# SDvp.net
KiCad netlist of a schematic drawn in Altium Designer
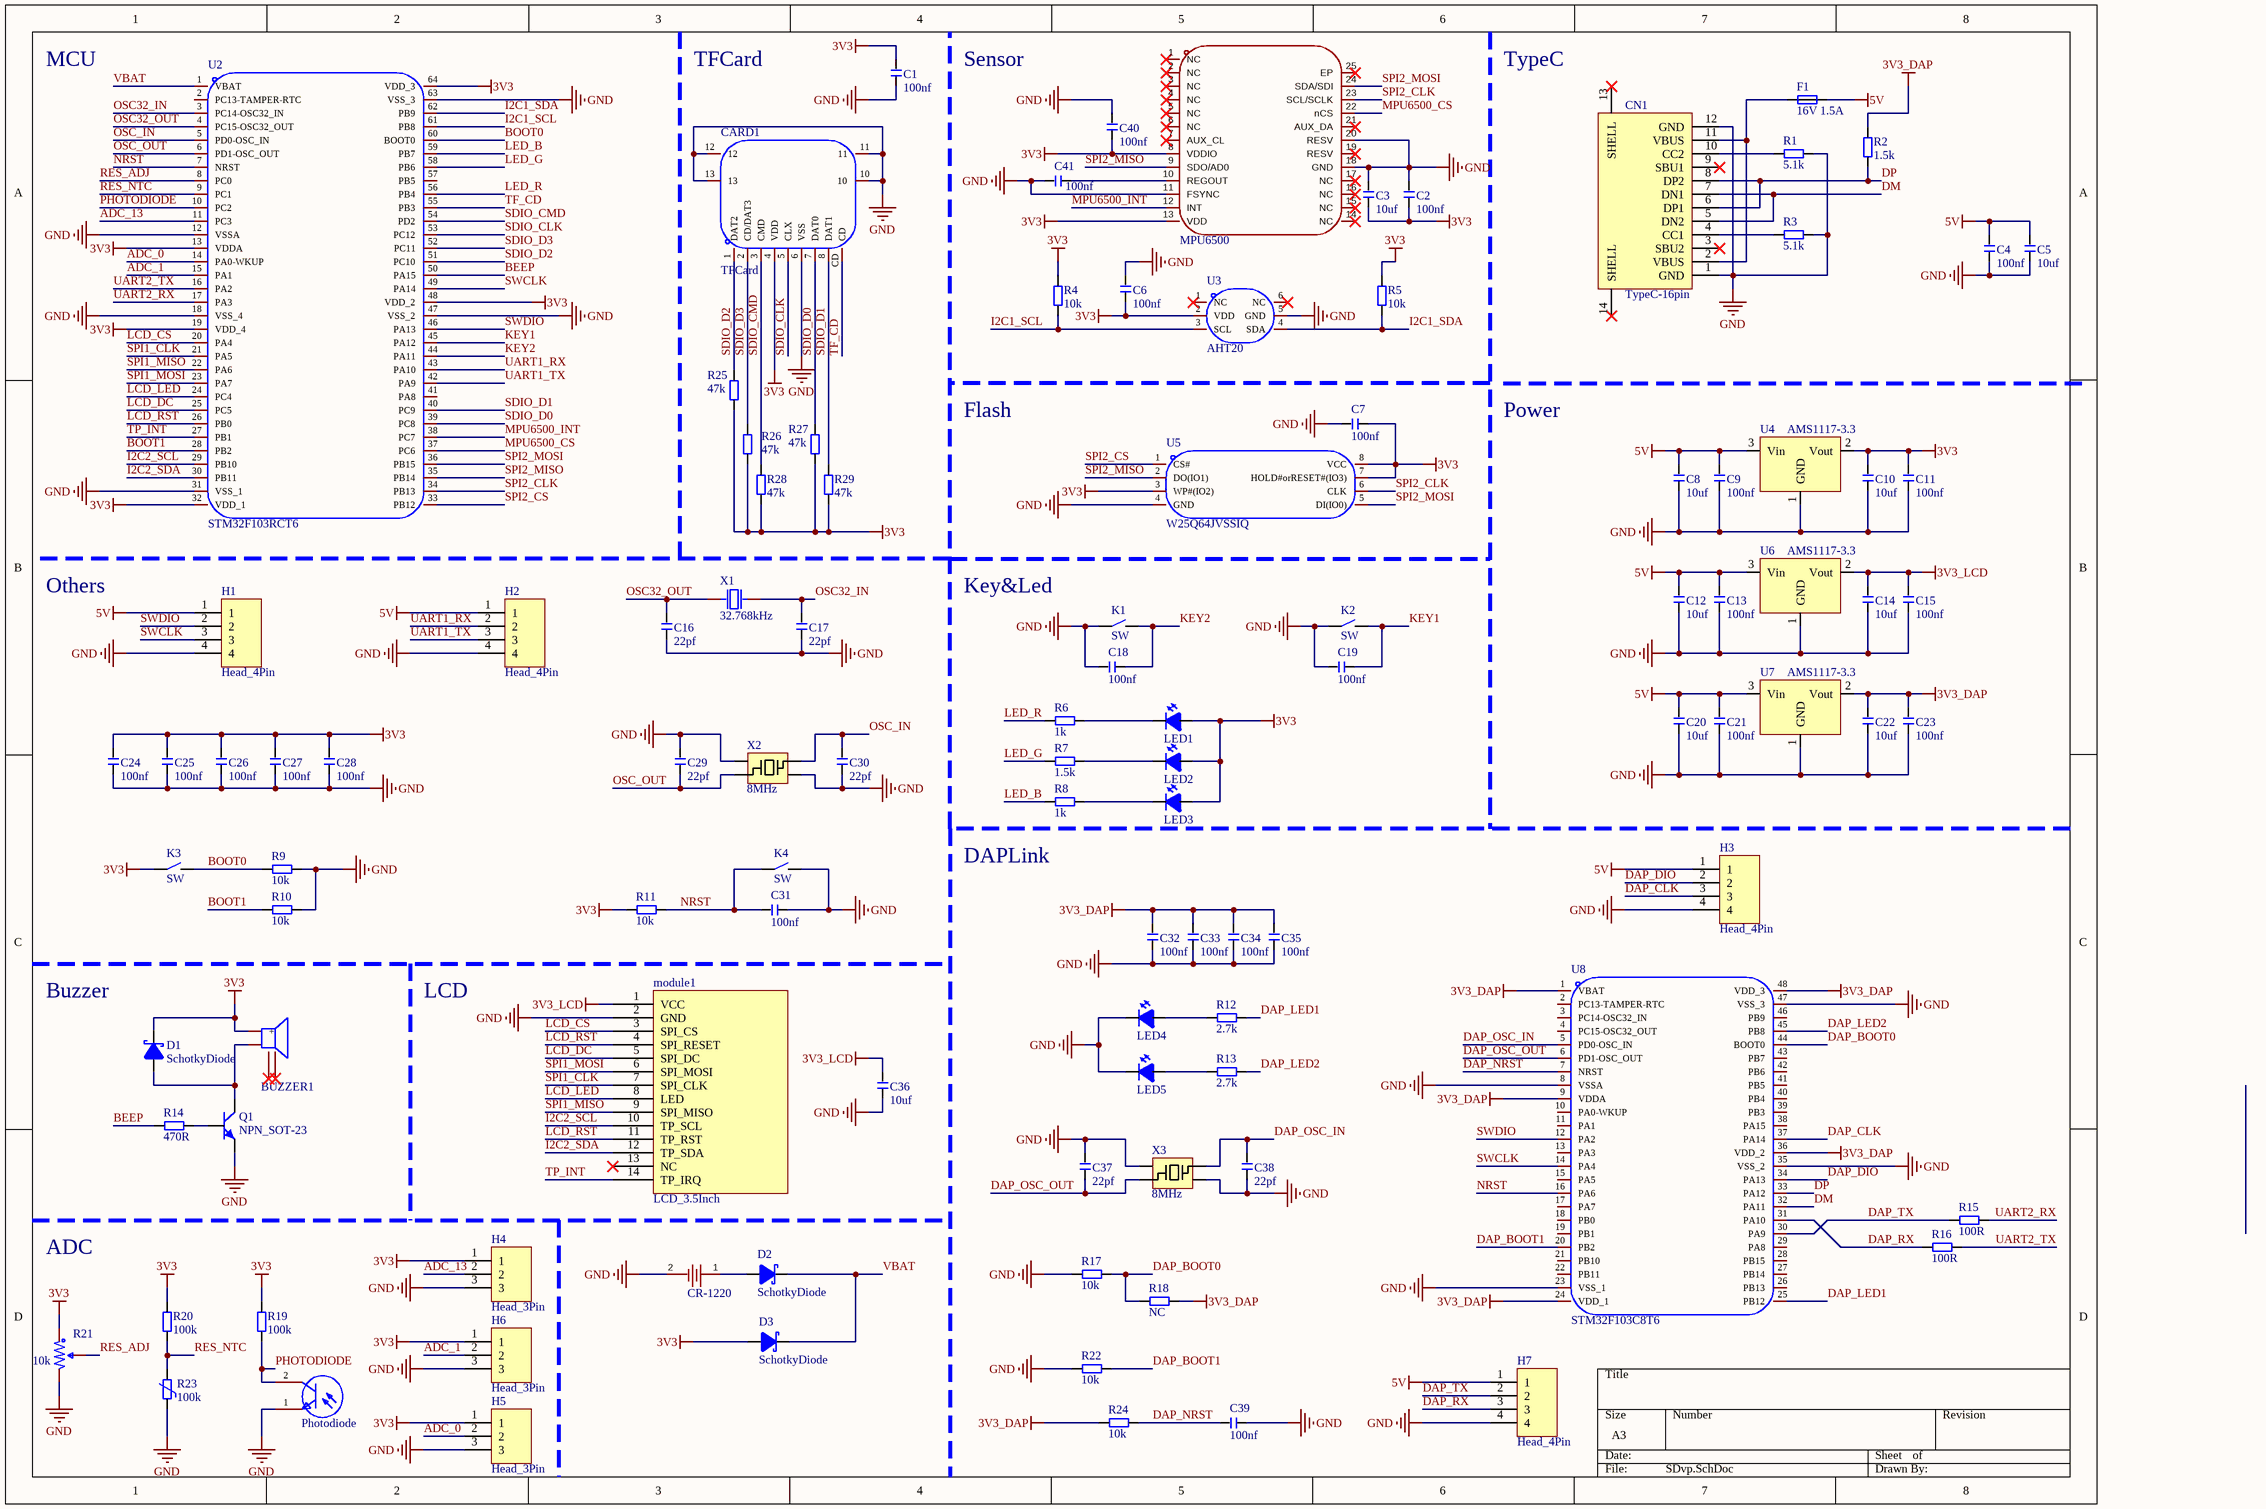
[diagram p0: SDvp.SchDoc]

(export (version "E")
  (design (tool "Eeschema 10.0.6"))
  (components
    (comp (ref "BUZZER1")
      (value "PassiveBuzzer")
      (footprint "BUZ-SMD_8530")
      (libsource (lib "IC") (part "PassiveBuzzer"))
    )
    (comp (ref "C1")
      (value "100nf")
      (footprint "CAP0603")
      (description "MLCC无极性电容")
      (libsource (lib "LCR") (part "Cap"))
    )
    (comp (ref "C2")
      (value "100nf")
      (footprint "CAP0603")
      (description "MLCC无极性电容")
      (libsource (lib "LCR") (part "Cap"))
    )
    (comp (ref "C3")
      (value "10uf")
      (footprint "CAP0603")
      (description "MLCC无极性电容")
      (libsource (lib "LCR") (part "Cap"))
    )
    (comp (ref "C4")
      (value "100nf")
      (footprint "CAP0603")
      (description "MLCC无极性电容")
      (libsource (lib "LCR") (part "Cap"))
    )
    (comp (ref "C5")
      (value "10uf")
      (footprint "CAP0603")
      (description "MLCC无极性电容")
      (libsource (lib "LCR") (part "Cap"))
    )
    (comp (ref "C6")
      (value "100nf")
      (footprint "CAP0603")
      (description "MLCC无极性电容")
      (libsource (lib "LCR") (part "Cap"))
    )
    (comp (ref "C7")
      (value "100nf")
      (footprint "CAP0603")
      (description "MLCC无极性电容")
      (libsource (lib "LCR") (part "Cap"))
    )
    (comp (ref "C8")
      (value "10uf")
      (footprint "CAP0603")
      (description "MLCC无极性电容")
      (libsource (lib "LCR") (part "Cap"))
    )
    (comp (ref "C9")
      (value "100nf")
      (footprint "CAP0603")
      (description "MLCC无极性电容")
      (libsource (lib "LCR") (part "Cap"))
    )
    (comp (ref "C10")
      (value "10uf")
      (footprint "CAP0603")
      (description "MLCC无极性电容")
      (libsource (lib "LCR") (part "Cap"))
    )
    (comp (ref "C11")
      (value "100nf")
      (footprint "CAP0603")
      (description "MLCC无极性电容")
      (libsource (lib "LCR") (part "Cap"))
    )
    (comp (ref "C12")
      (value "10uf")
      (footprint "CAP0603")
      (description "MLCC无极性电容")
      (libsource (lib "LCR") (part "Cap"))
    )
    (comp (ref "C13")
      (value "100nf")
      (footprint "CAP0603")
      (description "MLCC无极性电容")
      (libsource (lib "LCR") (part "Cap"))
    )
    (comp (ref "C14")
      (value "10uf")
      (footprint "CAP0603")
      (description "MLCC无极性电容")
      (libsource (lib "LCR") (part "Cap"))
    )
    (comp (ref "C15")
      (value "100nf")
      (footprint "CAP0603")
      (description "MLCC无极性电容")
      (libsource (lib "LCR") (part "Cap"))
    )
    (comp (ref "C16")
      (value "22pf")
      (footprint "CAP0603")
      (description "MLCC无极性电容")
      (libsource (lib "LCR") (part "Cap"))
    )
    (comp (ref "C17")
      (value "22pf")
      (footprint "CAP0603")
      (description "MLCC无极性电容")
      (libsource (lib "LCR") (part "Cap"))
    )
    (comp (ref "C18")
      (value "100nf")
      (footprint "CAP0603")
      (description "MLCC无极性电容")
      (libsource (lib "LCR") (part "Cap"))
    )
    (comp (ref "C19")
      (value "100nf")
      (footprint "CAP0603")
      (description "MLCC无极性电容")
      (libsource (lib "LCR") (part "Cap"))
    )
    (comp (ref "C20")
      (value "10uf")
      (footprint "CAP0603")
      (description "MLCC无极性电容")
      (libsource (lib "LCR") (part "Cap"))
    )
    (comp (ref "C21")
      (value "100nf")
      (footprint "CAP0603")
      (description "MLCC无极性电容")
      (libsource (lib "LCR") (part "Cap"))
    )
    (comp (ref "C22")
      (value "10uf")
      (footprint "CAP0603")
      (description "MLCC无极性电容")
      (libsource (lib "LCR") (part "Cap"))
    )
    (comp (ref "C23")
      (value "100nf")
      (footprint "CAP0603")
      (description "MLCC无极性电容")
      (libsource (lib "LCR") (part "Cap"))
    )
    (comp (ref "C24")
      (value "100nf")
      (footprint "CAP0603")
      (description "MLCC无极性电容")
      (libsource (lib "LCR") (part "Cap"))
    )
    (comp (ref "C25")
      (value "100nf")
      (footprint "CAP0603")
      (description "MLCC无极性电容")
      (libsource (lib "LCR") (part "Cap"))
    )
    (comp (ref "C26")
      (value "100nf")
      (footprint "CAP0603")
      (description "MLCC无极性电容")
      (libsource (lib "LCR") (part "Cap"))
    )
    (comp (ref "C27")
      (value "100nf")
      (footprint "CAP0603")
      (description "MLCC无极性电容")
      (libsource (lib "LCR") (part "Cap"))
    )
    (comp (ref "C28")
      (value "100nf")
      (footprint "CAP0603")
      (description "MLCC无极性电容")
      (libsource (lib "LCR") (part "Cap"))
    )
    (comp (ref "C29")
      (value "22pf")
      (footprint "CAP0603")
      (description "MLCC无极性电容")
      (libsource (lib "LCR") (part "Cap"))
    )
    (comp (ref "C30")
      (value "22pf")
      (footprint "CAP0603")
      (description "MLCC无极性电容")
      (libsource (lib "LCR") (part "Cap"))
    )
    (comp (ref "C31")
      (value "100nf")
      (footprint "CAP0603")
      (description "MLCC无极性电容")
      (libsource (lib "LCR") (part "Cap"))
    )
    (comp (ref "C32")
      (value "100nf")
      (footprint "CAP0603")
      (description "MLCC无极性电容")
      (libsource (lib "LCR") (part "Cap"))
    )
    (comp (ref "C33")
      (value "100nf")
      (footprint "CAP0603")
      (description "MLCC无极性电容")
      (libsource (lib "LCR") (part "Cap"))
    )
    (comp (ref "C34")
      (value "100nf")
      (footprint "CAP0603")
      (description "MLCC无极性电容")
      (libsource (lib "LCR") (part "Cap"))
    )
    (comp (ref "C35")
      (value "100nf")
      (footprint "CAP0603")
      (description "MLCC无极性电容")
      (libsource (lib "LCR") (part "Cap"))
    )
    (comp (ref "C36")
      (value "10uf")
      (footprint "CAP0603")
      (description "MLCC无极性电容")
      (libsource (lib "LCR") (part "Cap"))
    )
    (comp (ref "C37")
      (value "22pf")
      (footprint "CAP0603")
      (description "MLCC无极性电容")
      (libsource (lib "LCR") (part "Cap"))
    )
    (comp (ref "C38")
      (value "22pf")
      (footprint "CAP0603")
      (description "MLCC无极性电容")
      (libsource (lib "LCR") (part "Cap"))
    )
    (comp (ref "C39")
      (value "100nf")
      (footprint "CAP0603")
      (description "MLCC无极性电容")
      (libsource (lib "LCR") (part "Cap"))
    )
    (comp (ref "C40")
      (value "100nf")
      (footprint "CAP0603")
      (description "MLCC无极性电容")
      (libsource (lib "LCR") (part "Cap"))
    )
    (comp (ref "C41")
      (value "100nf")
      (footprint "CAP0603")
      (description "MLCC无极性电容")
      (libsource (lib "LCR") (part "Cap"))
    )
    (comp (ref "CARD1")
      (value "TFCard")
      (footprint "TF-SMD")
      (libsource (lib "Connector&Key") (part "TFCard"))
    )
    (comp (ref "CN1")
      (value "TypeC-16pin")
      (footprint "USB-C-SMD_16Pin")
      (libsource (lib "Connector&Key") (part "TypeC-16pin"))
    )
    (comp (ref "D1")
      (value "SchotkyDiode")
      (footprint "SOD-323")
      (description "肖特基二极管")
      (libsource (lib "Transistor") (part "SchotkyDiode"))
    )
    (comp (ref "D2")
      (value "SchotkyDiode")
      (footprint "SOD-323")
      (description "肖特基二极管")
      (libsource (lib "Transistor") (part "SchotkyDiode"))
    )
    (comp (ref "D3")
      (value "SchotkyDiode")
      (footprint "SOD-323")
      (description "肖特基二极管")
      (libsource (lib "Transistor") (part "SchotkyDiode"))
    )
    (comp (ref "F1")
      (value "16V 1.5A")
      (footprint "FUSE1206")
      (description "保险丝")
      (libsource (lib "LCR") (part "Fuse"))
    )
    (comp (ref "H1")
      (value "Head_4Pin")
      (footprint "2.54排针_4PIN")
      (libsource (lib "Connector&Key") (part "Head_4Pin"))
    )
    (comp (ref "H2")
      (value "Head_4Pin")
      (footprint "XH2.54_4Pin")
      (libsource (lib "Connector&Key") (part "Head_4Pin"))
    )
    (comp (ref "H3")
      (value "Head_4Pin")
      (footprint "2.54排针_4PIN")
      (libsource (lib "Connector&Key") (part "Head_4Pin"))
    )
    (comp (ref "H4")
      (value "Head_3Pin")
      (footprint "XH2.54_3Pin")
      (libsource (lib "Connector&Key") (part "Head_3Pin"))
    )
    (comp (ref "H5")
      (value "Head_3Pin")
      (footprint "XH2.54_3Pin")
      (libsource (lib "Connector&Key") (part "Head_3Pin"))
    )
    (comp (ref "H6")
      (value "Head_3Pin")
      (footprint "XH2.54_3Pin")
      (libsource (lib "Connector&Key") (part "Head_3Pin"))
    )
    (comp (ref "H7")
      (value "Head_4Pin")
      (footprint "2.54排针_4PIN")
      (libsource (lib "Connector&Key") (part "Head_4Pin"))
    )
    (comp (ref "K1")
      (value "SW")
      (footprint "SW-SMD_3425")
      (description "轻触开关")
      (libsource (lib "Connector&Key") (part "SW"))
    )
    (comp (ref "K2")
      (value "SW")
      (footprint "SW-SMD_3425")
      (description "轻触开关")
      (libsource (lib "Connector&Key") (part "SW"))
    )
    (comp (ref "K3")
      (value "SW")
      (footprint "SW-SMD_3425")
      (description "轻触开关")
      (libsource (lib "Connector&Key") (part "SW"))
    )
    (comp (ref "K4")
      (value "SW")
      (footprint "SW-SMD_3425")
      (description "轻触开关")
      (libsource (lib "Connector&Key") (part "SW"))
    )
    (comp (ref "LED1")
      (value "LED_R")
      (footprint "LED0603")
      (description "发光二极管")
      (libsource (lib "Transistor") (part "LED"))
    )
    (comp (ref "LED2")
      (value "LED_G")
      (footprint "LED0603")
      (description "发光二极管")
      (libsource (lib "Transistor") (part "LED"))
    )
    (comp (ref "LED3")
      (value "LED_B")
      (footprint "LED0603")
      (description "发光二极管")
      (libsource (lib "Transistor") (part "LED"))
    )
    (comp (ref "LED4")
      (value "LED")
      (footprint "LED0603")
      (description "发光二极管")
      (libsource (lib "Transistor") (part "LED"))
    )
    (comp (ref "LED5")
      (value "LED")
      (footprint "LED0603")
      (description "发光二极管")
      (libsource (lib "Transistor") (part "LED"))
    )
    (comp (ref "module1")
      (value "LCD_3.5Inch")
      (footprint "LCD_3.5Inch")
      (libsource (lib "module") (part "LCD_3.5Inch"))
    )
    (comp (ref "Q1")
      (value "NPN_SOT-23")
      (footprint "SOT-23-3")
      (description "三极管")
      (libsource (lib "Transistor") (part "NPN_SOT-23"))
    )
    (comp (ref "R1")
      (value "5.1k")
      (footprint "RES0603")
      (description "电阻")
      (libsource (lib "LCR") (part "Res"))
    )
    (comp (ref "R2")
      (value "1.5k")
      (footprint "RES0603")
      (description "电阻")
      (libsource (lib "LCR") (part "Res"))
    )
    (comp (ref "R3")
      (value "5.1k")
      (footprint "RES0603")
      (description "电阻")
      (libsource (lib "LCR") (part "Res"))
    )
    (comp (ref "R4")
      (value "10k")
      (footprint "RES0603")
      (description "电阻")
      (libsource (lib "LCR") (part "Res"))
    )
    (comp (ref "R5")
      (value "10k")
      (footprint "RES0603")
      (description "电阻")
      (libsource (lib "LCR") (part "Res"))
    )
    (comp (ref "R6")
      (value "1k")
      (footprint "RES0603")
      (description "电阻")
      (libsource (lib "LCR") (part "Res"))
    )
    (comp (ref "R7")
      (value "1.5k")
      (footprint "RES0603")
      (description "电阻")
      (libsource (lib "LCR") (part "Res"))
    )
    (comp (ref "R8")
      (value "1k")
      (footprint "RES0603")
      (description "电阻")
      (libsource (lib "LCR") (part "Res"))
    )
    (comp (ref "R9")
      (value "10k")
      (footprint "RES0603")
      (description "电阻")
      (libsource (lib "LCR") (part "Res"))
    )
    (comp (ref "R10")
      (value "10k")
      (footprint "RES0603")
      (description "电阻")
      (libsource (lib "LCR") (part "Res"))
    )
    (comp (ref "R11")
      (value "10k")
      (footprint "RES0603")
      (description "电阻")
      (libsource (lib "LCR") (part "Res"))
    )
    (comp (ref "R12")
      (value "2.7k")
      (footprint "RES0603")
      (description "电阻")
      (libsource (lib "LCR") (part "Res"))
    )
    (comp (ref "R13")
      (value "2.7k")
      (footprint "RES0603")
      (description "电阻")
      (libsource (lib "LCR") (part "Res"))
    )
    (comp (ref "R14")
      (value "470R")
      (footprint "RES0603")
      (description "电阻")
      (libsource (lib "LCR") (part "Res"))
    )
    (comp (ref "R15")
      (value "100R")
      (footprint "RES0603")
      (description "电阻")
      (libsource (lib "LCR") (part "Res"))
    )
    (comp (ref "R16")
      (value "100R")
      (footprint "RES0603")
      (description "电阻")
      (libsource (lib "LCR") (part "Res"))
    )
    (comp (ref "R17")
      (value "10k")
      (footprint "RES0603")
      (description "电阻")
      (libsource (lib "LCR") (part "Res"))
    )
    (comp (ref "R18")
      (value "NC")
      (footprint "RES0603")
      (description "电阻")
      (libsource (lib "LCR") (part "Res"))
    )
    (comp (ref "R19")
      (value "100k")
      (footprint "RES0603")
      (description "电阻")
      (libsource (lib "LCR") (part "Res"))
    )
    (comp (ref "R20")
      (value "100k")
      (footprint "RES0603")
      (description "电阻")
      (libsource (lib "LCR") (part "Res"))
    )
    (comp (ref "R21")
      (value "10k")
      (footprint "RES-ADJ-BuleWhite")
      (description "可调电位器")
      (libsource (lib "LCR") (part "RES_ADJ"))
    )
    (comp (ref "R22")
      (value "10k")
      (footprint "RES0603")
      (description "电阻")
      (libsource (lib "LCR") (part "Res"))
    )
    (comp (ref "R23")
      (value "100k")
      (footprint "RES0603")
      (description "热敏电阻")
      (libsource (lib "LCR") (part "RES_NTC"))
    )
    (comp (ref "R24")
      (value "10k")
      (footprint "RES0603")
      (description "电阻")
      (libsource (lib "LCR") (part "Res"))
    )
    (comp (ref "R25")
      (value "47k")
      (footprint "RES0603")
      (description "电阻")
      (libsource (lib "LCR") (part "Res"))
    )
    (comp (ref "R26")
      (value "47k")
      (footprint "RES0603")
      (description "电阻")
      (libsource (lib "LCR") (part "Res"))
    )
    (comp (ref "R27")
      (value "47k")
      (footprint "RES0603")
      (description "电阻")
      (libsource (lib "LCR") (part "Res"))
    )
    (comp (ref "R28")
      (value "47k")
      (footprint "RES0603")
      (description "电阻")
      (libsource (lib "LCR") (part "Res"))
    )
    (comp (ref "R29")
      (value "47k")
      (footprint "RES0603")
      (description "电阻")
      (libsource (lib "LCR") (part "Res"))
    )
    (comp (ref "U1")
      (value "MPU6500")
      (footprint "QFN-24")
      (description "陀螺仪芯片")
      (libsource (lib "IC") (part "MPU6500"))
    )
    (comp (ref "U2")
      (value "STM32F103RCT6")
      (footprint "LQFP-64")
      (description "STM32F103")
      (libsource (lib "IC") (part "STM32F103RCT6"))
    )
    (comp (ref "U3")
      (value "AHT20")
      (footprint "AHT20")
      (description "温湿度芯片")
      (libsource (lib "IC") (part "AHT20"))
    )
    (comp (ref "U4")
      (value "AMS1117-3.3")
      (footprint "SOT223")
      (description "降压芯片")
      (libsource (lib "IC") (part "AMS1117-3.3"))
    )
    (comp (ref "U5")
      (value "W25Q64JVSSIQ")
      (footprint "SOIC-8")
      (description "FLASH芯片")
      (libsource (lib "IC") (part "W25Q64JVSSIQ"))
    )
    (comp (ref "U6")
      (value "AMS1117-3.3")
      (footprint "SOT223")
      (description "降压芯片")
      (libsource (lib "IC") (part "AMS1117-3.3"))
    )
    (comp (ref "U7")
      (value "AMS1117-3.3")
      (footprint "SOT223")
      (description "降压芯片")
      (libsource (lib "IC") (part "AMS1117-3.3"))
    )
    (comp (ref "U8")
      (value "STM32F103C8T6")
      (footprint "LQFP-48")
      (description "STM32F103")
      (libsource (lib "IC") (part "STM32F103C8T6"))
    )
    (comp (ref "U9")
      (value "Photodiode")
      (footprint "Photodiode0603")
      (description "光敏二极管")
      (libsource (lib "Transistor") (part "Photodiode"))
    )
    (comp (ref "U10")
      (value "CR-1220")
      (footprint "BAT-SMD_CR1220")
      (description "CR-1220电池座")
      (libsource (lib "Connector&Key") (part "CR-1220"))
    )
    (comp (ref "X1")
      (value "32.768kHz")
      (footprint "XTAL_3215")
      (description "无源晶振3215")
      (libsource (lib "IC") (part "XTAL_3215"))
    )
    (comp (ref "X2") (value "8MHz") (footprint "XTAL_3225") (libsource (lib "IC") (part "XTAL_无源4脚")))
    (comp (ref "X3") (value "8MHz") (footprint "XTAL_3225") (libsource (lib "IC") (part "XTAL_无源4脚")))
  )
  (nets
    (net (code "1") (name "/ADC_0") (class "Default")
      (node (ref "H5") (pin "2") (pinfunction "2_2") (pintype "passive"))
      (node (ref "U2") (pin "14") (pinfunction "PA0-WKUP_14") (pintype "passive"))
    )
    (net (code "2") (name "/ADC_1") (class "Default")
      (node (ref "H6") (pin "2") (pinfunction "2_2") (pintype "passive"))
      (node (ref "U2") (pin "15") (pinfunction "PA1_15") (pintype "passive"))
    )
    (net (code "3") (name "/ADC_13") (class "Default")
      (node (ref "H4") (pin "2") (pinfunction "2_2") (pintype "passive"))
      (node (ref "U2") (pin "11") (pinfunction "PC3_11") (pintype "passive"))
    )
    (net (code "4") (name "/BEEP") (class "Default")
      (node (ref "R14") (pin "1") (pinfunction "1_1") (pintype "passive"))
      (node (ref "U2") (pin "50") (pinfunction "PA15_50") (pintype "passive"))
    )
    (net (code "5") (name "/BOOT0") (class "Default")
      (node (ref "K3") (pin "2") (pinfunction "2_2") (pintype "passive"))
      (node (ref "R9") (pin "1") (pinfunction "1_1") (pintype "passive"))
      (node (ref "U2") (pin "60") (pinfunction "BOOT0_60") (pintype "passive"))
    )
    (net (code "6") (name "/BOOT1") (class "Default")
      (node (ref "R10") (pin "1") (pinfunction "1_1") (pintype "passive"))
      (node (ref "U2") (pin "28") (pinfunction "PB2_28") (pintype "passive"))
    )
    (net (code "7") (name "/DAP_BOOT0") (class "Default")
      (node (ref "R17") (pin "2") (pinfunction "2_2") (pintype "passive"))
      (node (ref "R18") (pin "1") (pinfunction "1_1") (pintype "passive"))
      (node (ref "U8") (pin "44") (pinfunction "BOOT0_44") (pintype "passive"))
    )
    (net (code "8") (name "/DAP_BOOT1") (class "Default")
      (node (ref "R22") (pin "2") (pinfunction "2_2") (pintype "passive"))
      (node (ref "U8") (pin "20") (pinfunction "PB2_20") (pintype "passive"))
    )
    (net (code "9") (name "/DAP_CLK") (class "Default")
      (node (ref "H3") (pin "3") (pinfunction "3_3") (pintype "passive"))
      (node (ref "U8") (pin "37") (pinfunction "PA14_37") (pintype "passive"))
    )
    (net (code "10") (name "/DAP_DIO") (class "Default")
      (node (ref "H3") (pin "2") (pinfunction "2_2") (pintype "passive"))
      (node (ref "U8") (pin "34") (pinfunction "PA13_34") (pintype "passive"))
    )
    (net (code "11") (name "/DAP_LED1") (class "Default")
      (node (ref "R12") (pin "2") (pinfunction "2_2") (pintype "passive"))
      (node (ref "U8") (pin "25") (pinfunction "PB12_25") (pintype "passive"))
    )
    (net (code "12") (name "/DAP_LED2") (class "Default")
      (node (ref "R13") (pin "2") (pinfunction "2_2") (pintype "passive"))
      (node (ref "U8") (pin "45") (pinfunction "PB8_45") (pintype "passive"))
    )
    (net (code "13") (name "/DAP_NRST") (class "Default")
      (node (ref "C39") (pin "1") (pinfunction "1_1") (pintype "passive"))
      (node (ref "R24") (pin "2") (pinfunction "2_2") (pintype "passive"))
      (node (ref "U8") (pin "7") (pinfunction "NRST_7") (pintype "passive"))
    )
    (net (code "14") (name "/DAP_OSC_IN") (class "Default")
      (node (ref "C38") (pin "2") (pinfunction "2_2") (pintype "passive"))
      (node (ref "U8") (pin "5") (pinfunction "PD0-OSC_IN_5") (pintype "passive"))
      (node (ref "X3") (pin "3") (pinfunction "3_3") (pintype "passive"))
    )
    (net (code "15") (name "/DAP_OSC_OUT") (class "Default")
      (node (ref "C37") (pin "1") (pinfunction "1_1") (pintype "passive"))
      (node (ref "U8") (pin "6") (pinfunction "PD1-OSC_OUT_6") (pintype "passive"))
      (node (ref "X3") (pin "1") (pinfunction "1_1") (pintype "passive"))
    )
    (net (code "16") (name "/DAP_RX") (class "Default")
      (node (ref "H7") (pin "3") (pinfunction "3_3") (pintype "passive"))
      (node (ref "R16") (pin "1") (pinfunction "1_1") (pintype "passive"))
      (node (ref "U8") (pin "31") (pinfunction "PA10_31") (pintype "passive"))
    )
    (net (code "17") (name "/DAP_TX") (class "Default")
      (node (ref "H7") (pin "2") (pinfunction "2_2") (pintype "passive"))
      (node (ref "R15") (pin "1") (pinfunction "1_1") (pintype "passive"))
      (node (ref "U8") (pin "30") (pinfunction "PA9_30") (pintype "passive"))
    )
    (net (code "18") (name "/DM") (class "Default")
      (node (ref "CN1") (pin "5") (pinfunction "DN2_5") (pintype "passive"))
      (node (ref "CN1") (pin "7") (pinfunction "DN1_7") (pintype "passive"))
      (node (ref "U8") (pin "32") (pinfunction "PA11_32") (pintype "passive"))
    )
    (net (code "19") (name "/DP") (class "Default")
      (node (ref "CN1") (pin "6") (pinfunction "DP1_6") (pintype "passive"))
      (node (ref "CN1") (pin "8") (pinfunction "DP2_8") (pintype "passive"))
      (node (ref "R2") (pin "2") (pinfunction "2_2") (pintype "passive"))
      (node (ref "U8") (pin "33") (pinfunction "PA12_33") (pintype "passive"))
    )
    (net (code "20") (name "/I2C1_SCL") (class "Default")
      (node (ref "R4") (pin "1") (pinfunction "1_1") (pintype "passive"))
      (node (ref "U2") (pin "61") (pinfunction "PB8_61") (pintype "passive"))
      (node (ref "U3") (pin "3") (pinfunction "SCL_3") (pintype "passive"))
    )
    (net (code "21") (name "/I2C1_SDA") (class "Default")
      (node (ref "R5") (pin "1") (pinfunction "1_1") (pintype "passive"))
      (node (ref "U2") (pin "62") (pinfunction "PB9_62") (pintype "passive"))
      (node (ref "U3") (pin "4") (pinfunction "SDA_4") (pintype "passive"))
    )
    (net (code "22") (name "/I2C2_SCL") (class "Default")
      (node (ref "U2") (pin "29") (pinfunction "PB10_29") (pintype "passive"))
      (node (ref "module1") (pin "10") (pinfunction "TP_SCL_10") (pintype "passive"))
    )
    (net (code "23") (name "/I2C2_SDA") (class "Default")
      (node (ref "U2") (pin "30") (pinfunction "PB11_30") (pintype "passive"))
      (node (ref "module1") (pin "12") (pinfunction "TP_SDA_12") (pintype "passive"))
    )
    (net (code "24") (name "/KEY1") (class "Default")
      (node (ref "C19") (pin "1") (pinfunction "1_1") (pintype "passive"))
      (node (ref "K2") (pin "2") (pinfunction "2_2") (pintype "passive"))
      (node (ref "U2") (pin "45") (pinfunction "PA12_45") (pintype "passive"))
    )
    (net (code "25") (name "/KEY2") (class "Default")
      (node (ref "C18") (pin "1") (pinfunction "1_1") (pintype "passive"))
      (node (ref "K1") (pin "2") (pinfunction "2_2") (pintype "passive"))
      (node (ref "U2") (pin "44") (pinfunction "PA11_44") (pintype "passive"))
    )
    (net (code "26") (name "/LCD_CS") (class "Default")
      (node (ref "U2") (pin "20") (pinfunction "PA4_20") (pintype "passive"))
      (node (ref "module1") (pin "3") (pinfunction "SPI_CS_3") (pintype "passive"))
    )
    (net (code "27") (name "/LCD_DC") (class "Default")
      (node (ref "U2") (pin "25") (pinfunction "PC5_25") (pintype "passive"))
      (node (ref "module1") (pin "5") (pinfunction "SPI_DC_5") (pintype "passive"))
    )
    (net (code "28") (name "/LCD_LED") (class "Default")
      (node (ref "U2") (pin "24") (pinfunction "PC4_24") (pintype "passive"))
      (node (ref "module1") (pin "8") (pinfunction "LED_8") (pintype "passive"))
    )
    (net (code "29") (name "/LCD_RST") (class "Default")
      (node (ref "U2") (pin "26") (pinfunction "PB0_26") (pintype "passive"))
      (node (ref "module1") (pin "11") (pinfunction "TP_RST_11") (pintype "passive"))
      (node (ref "module1") (pin "4") (pinfunction "SPI_RESET_4") (pintype "passive"))
    )
    (net (code "30") (name "/LED_B") (class "Default")
      (node (ref "R8") (pin "2") (pinfunction "2_2") (pintype "passive"))
      (node (ref "U2") (pin "59") (pinfunction "PB7_59") (pintype "passive"))
    )
    (net (code "31") (name "/LED_G") (class "Default")
      (node (ref "R7") (pin "2") (pinfunction "2_2") (pintype "passive"))
      (node (ref "U2") (pin "58") (pinfunction "PB6_58") (pintype "passive"))
    )
    (net (code "32") (name "/LED_R") (class "Default")
      (node (ref "R6") (pin "1") (pinfunction "1_1") (pintype "passive"))
      (node (ref "U2") (pin "56") (pinfunction "PB4_56") (pintype "passive"))
    )
    (net (code "33") (name "/MPU6500_CS") (class "Default")
      (node (ref "U1") (pin "22") (pinfunction "nCS_22") (pintype "passive"))
      (node (ref "U2") (pin "37") (pinfunction "PC6_37") (pintype "passive"))
    )
    (net (code "34") (name "/MPU6500_INT") (class "Default")
      (node (ref "U1") (pin "12") (pinfunction "INT_12") (pintype "passive"))
      (node (ref "U2") (pin "38") (pinfunction "PC7_38") (pintype "passive"))
    )
    (net (code "35") (name "/NRST") (class "Default")
      (node (ref "C31") (pin "1") (pinfunction "1_1") (pintype "passive"))
      (node (ref "K4") (pin "1") (pinfunction "1_1") (pintype "passive"))
      (node (ref "R11") (pin "2") (pinfunction "2_2") (pintype "passive"))
      (node (ref "U2") (pin "7") (pinfunction "NRST_7") (pintype "passive"))
      (node (ref "U8") (pin "16") (pinfunction "PA6_16") (pintype "passive"))
    )
    (net (code "36") (name "/OSC32_IN") (class "Default")
      (node (ref "C17") (pin "2") (pinfunction "2_2") (pintype "passive"))
      (node (ref "U2") (pin "3") (pinfunction "PC14-OSC32_IN_3") (pintype "passive"))
      (node (ref "X1") (pin "2") (pinfunction "OSC2_2") (pintype "passive"))
    )
    (net (code "37") (name "/OSC32_OUT") (class "Default")
      (node (ref "C16") (pin "2") (pinfunction "2_2") (pintype "passive"))
      (node (ref "U2") (pin "4") (pinfunction "PC15-OSC32_OUT_4") (pintype "passive"))
      (node (ref "X1") (pin "1") (pinfunction "OSC1_1") (pintype "passive"))
    )
    (net (code "38") (name "/OSC_IN") (class "Default")
      (node (ref "C30") (pin "2") (pinfunction "2_2") (pintype "passive"))
      (node (ref "U2") (pin "5") (pinfunction "PD0-OSC_IN_5") (pintype "passive"))
      (node (ref "X2") (pin "3") (pinfunction "3_3") (pintype "passive"))
    )
    (net (code "39") (name "/OSC_OUT") (class "Default")
      (node (ref "C29") (pin "1") (pinfunction "1_1") (pintype "passive"))
      (node (ref "U2") (pin "6") (pinfunction "PD1-OSC_OUT_6") (pintype "passive"))
      (node (ref "X2") (pin "1") (pinfunction "1_1") (pintype "passive"))
    )
    (net (code "40") (name "/PHOTODIODE") (class "Default")
      (node (ref "R19") (pin "1") (pinfunction "1_1") (pintype "passive"))
      (node (ref "U2") (pin "10") (pinfunction "PC2_10") (pintype "passive"))
      (node (ref "U9") (pin "2") (pinfunction "C_2") (pintype "passive"))
    )
    (net (code "41") (name "/RES_ADJ") (class "Default")
      (node (ref "R21") (pin "2") (pinfunction "2_2") (pintype "passive"))
      (node (ref "U2") (pin "8") (pinfunction "PC0_8") (pintype "passive"))
    )
    (net (code "42") (name "/RES_NTC") (class "Default")
      (node (ref "R20") (pin "1") (pinfunction "1_1") (pintype "passive"))
      (node (ref "R23") (pin "2") (pinfunction "2_2") (pintype "passive"))
      (node (ref "U2") (pin "9") (pinfunction "PC1_9") (pintype "passive"))
    )
    (net (code "43") (name "/SDIO_CLK") (class "Default")
      (node (ref "CARD1") (pin "5") (pinfunction "CLX_5") (pintype "passive"))
      (node (ref "U2") (pin "53") (pinfunction "PC12_53") (pintype "passive"))
    )
    (net (code "44") (name "/SDIO_CMD") (class "Default")
      (node (ref "CARD1") (pin "3") (pinfunction "CMD_3") (pintype "passive"))
      (node (ref "R28") (pin "2") (pinfunction "2_2") (pintype "passive"))
      (node (ref "U2") (pin "54") (pinfunction "PD2_54") (pintype "passive"))
    )
    (net (code "45") (name "/SDIO_D0") (class "Default")
      (node (ref "CARD1") (pin "7") (pinfunction "DAT0_7") (pintype "passive"))
      (node (ref "R27") (pin "2") (pinfunction "2_2") (pintype "passive"))
      (node (ref "U2") (pin "39") (pinfunction "PC8_39") (pintype "passive"))
    )
    (net (code "46") (name "/SDIO_D1") (class "Default")
      (node (ref "CARD1") (pin "8") (pinfunction "DAT1_8") (pintype "passive"))
      (node (ref "R29") (pin "2") (pinfunction "2_2") (pintype "passive"))
      (node (ref "U2") (pin "40") (pinfunction "PC9_40") (pintype "passive"))
    )
    (net (code "47") (name "/SDIO_D2") (class "Default")
      (node (ref "CARD1") (pin "1") (pinfunction "DAT2_1") (pintype "passive"))
      (node (ref "R25") (pin "2") (pinfunction "2_2") (pintype "passive"))
      (node (ref "U2") (pin "51") (pinfunction "PC10_51") (pintype "passive"))
    )
    (net (code "48") (name "/SDIO_D3") (class "Default")
      (node (ref "CARD1") (pin "2") (pinfunction "CD/DAT3_2") (pintype "passive"))
      (node (ref "R26") (pin "2") (pinfunction "2_2") (pintype "passive"))
      (node (ref "U2") (pin "52") (pinfunction "PC11_52") (pintype "passive"))
    )
    (net (code "49") (name "/SPI1_CLK") (class "Default")
      (node (ref "U2") (pin "21") (pinfunction "PA5_21") (pintype "passive"))
      (node (ref "module1") (pin "7") (pinfunction "SPI_CLK_7") (pintype "passive"))
    )
    (net (code "50") (name "/SPI1_MISO") (class "Default")
      (node (ref "U2") (pin "22") (pinfunction "PA6_22") (pintype "passive"))
      (node (ref "module1") (pin "9") (pinfunction "SPI_MISO_9") (pintype "passive"))
    )
    (net (code "51") (name "/SPI1_MOSI") (class "Default")
      (node (ref "U2") (pin "23") (pinfunction "PA7_23") (pintype "passive"))
      (node (ref "module1") (pin "6") (pinfunction "SPI_MOSI_6") (pintype "passive"))
    )
    (net (code "52") (name "/SPI2_CLK") (class "Default")
      (node (ref "U1") (pin "23") (pinfunction "SCL/SCLK_23") (pintype "passive"))
      (node (ref "U2") (pin "34") (pinfunction "PB13_34") (pintype "passive"))
      (node (ref "U5") (pin "6") (pinfunction "CLK_6") (pintype "passive"))
    )
    (net (code "53") (name "/SPI2_CS") (class "Default")
      (node (ref "U2") (pin "33") (pinfunction "PB12_33") (pintype "passive"))
      (node (ref "U5") (pin "1") (pinfunction "CS#_1") (pintype "passive"))
    )
    (net (code "54") (name "/SPI2_MISO") (class "Default")
      (node (ref "U1") (pin "9") (pinfunction "SDO/AD0_9") (pintype "passive"))
      (node (ref "U2") (pin "35") (pinfunction "PB14_35") (pintype "passive"))
      (node (ref "U5") (pin "2") (pinfunction "DO(IO1)_2") (pintype "passive"))
    )
    (net (code "55") (name "/SPI2_MOSI") (class "Default")
      (node (ref "U1") (pin "24") (pinfunction "SDA/SDI_24") (pintype "passive"))
      (node (ref "U2") (pin "36") (pinfunction "PB15_36") (pintype "passive"))
      (node (ref "U5") (pin "5") (pinfunction "DI(IO0)_5") (pintype "passive"))
    )
    (net (code "56") (name "/SWCLK") (class "Default")
      (node (ref "H1") (pin "3") (pinfunction "3_3") (pintype "passive"))
      (node (ref "U2") (pin "49") (pinfunction "PA14_49") (pintype "passive"))
      (node (ref "U8") (pin "14") (pinfunction "PA4_14") (pintype "passive"))
    )
    (net (code "57") (name "/SWDIO") (class "Default")
      (node (ref "H1") (pin "2") (pinfunction "2_2") (pintype "passive"))
      (node (ref "U2") (pin "46") (pinfunction "PA13_46") (pintype "passive"))
      (node (ref "U8") (pin "12") (pinfunction "PA2_12") (pintype "passive"))
    )
    (net (code "58") (name "/TF_CD") (class "Default")
      (node (ref "CARD1") (pin "CD") (pinfunction "CD_CD") (pintype "passive"))
      (node (ref "U2") (pin "55") (pinfunction "PB3_55") (pintype "passive"))
    )
    (net (code "59") (name "/TP_INT") (class "Default")
      (node (ref "U2") (pin "27") (pinfunction "PB1_27") (pintype "passive"))
      (node (ref "module1") (pin "14") (pinfunction "TP_IRQ_14") (pintype "passive"))
    )
    (net (code "60") (name "/UART1_RX") (class "Default")
      (node (ref "H2") (pin "2") (pinfunction "2_2") (pintype "passive"))
      (node (ref "U2") (pin "43") (pinfunction "PA10_43") (pintype "passive"))
    )
    (net (code "61") (name "/UART1_TX") (class "Default")
      (node (ref "H2") (pin "3") (pinfunction "3_3") (pintype "passive"))
      (node (ref "U2") (pin "42") (pinfunction "PA9_42") (pintype "passive"))
    )
    (net (code "62") (name "/UART2_RX") (class "Default")
      (node (ref "R15") (pin "2") (pinfunction "2_2") (pintype "passive"))
      (node (ref "U2") (pin "17") (pinfunction "PA3_17") (pintype "passive"))
    )
    (net (code "63") (name "/UART2_TX") (class "Default")
      (node (ref "R16") (pin "2") (pinfunction "2_2") (pintype "passive"))
      (node (ref "U2") (pin "16") (pinfunction "PA2_16") (pintype "passive"))
    )
    (net (code "64") (name "/VBAT") (class "Default")
      (node (ref "D2") (pin "2") (pinfunction "2_2") (pintype "passive"))
      (node (ref "D3") (pin "2") (pinfunction "2_2") (pintype "passive"))
      (node (ref "U2") (pin "1") (pinfunction "VBAT_1") (pintype "passive"))
    )
    (net (code "65") (name "3V3") (class "Default")
      (node (ref "BUZZER1") (pin "1") (pinfunction "+_1") (pintype "passive"))
      (node (ref "C1") (pin "2") (pinfunction "2_2") (pintype "passive"))
      (node (ref "C10") (pin "2") (pinfunction "2_2") (pintype "passive"))
      (node (ref "C11") (pin "2") (pinfunction "2_2") (pintype "passive"))
      (node (ref "C2") (pin "1") (pinfunction "1_1") (pintype "passive"))
      (node (ref "C24") (pin "2") (pinfunction "2_2") (pintype "passive"))
      (node (ref "C25") (pin "2") (pinfunction "2_2") (pintype "passive"))
      (node (ref "C26") (pin "2") (pinfunction "2_2") (pintype "passive"))
      (node (ref "C27") (pin "2") (pinfunction "2_2") (pintype "passive"))
      (node (ref "C28") (pin "2") (pinfunction "2_2") (pintype "passive"))
      (node (ref "C3") (pin "1") (pinfunction "1_1") (pintype "passive"))
      (node (ref "C40") (pin "1") (pinfunction "1_1") (pintype "passive"))
      (node (ref "C6") (pin "1") (pinfunction "1_1") (pintype "passive"))
      (node (ref "C7") (pin "1") (pinfunction "1_1") (pintype "passive"))
      (node (ref "CARD1") (pin "4") (pinfunction "VDD_4") (pintype "passive"))
      (node (ref "D1") (pin "2") (pinfunction "2_2") (pintype "passive"))
      (node (ref "D3") (pin "1") (pinfunction "1_1") (pintype "passive"))
      (node (ref "H4") (pin "1") (pinfunction "1_1") (pintype "passive"))
      (node (ref "H5") (pin "1") (pinfunction "1_1") (pintype "passive"))
      (node (ref "H6") (pin "1") (pinfunction "1_1") (pintype "passive"))
      (node (ref "K3") (pin "1") (pinfunction "1_1") (pintype "passive"))
      (node (ref "LED1") (pin "2") (pinfunction "2_2") (pintype "passive"))
      (node (ref "LED2") (pin "2") (pinfunction "2_2") (pintype "passive"))
      (node (ref "LED3") (pin "2") (pinfunction "2_2") (pintype "passive"))
      (node (ref "R11") (pin "1") (pinfunction "1_1") (pintype "passive"))
      (node (ref "R19") (pin "2") (pinfunction "2_2") (pintype "passive"))
      (node (ref "R20") (pin "2") (pinfunction "2_2") (pintype "passive"))
      (node (ref "R21") (pin "1") (pinfunction "1_1") (pintype "passive"))
      (node (ref "R25") (pin "1") (pinfunction "1_1") (pintype "passive"))
      (node (ref "R26") (pin "1") (pinfunction "1_1") (pintype "passive"))
      (node (ref "R27") (pin "1") (pinfunction "1_1") (pintype "passive"))
      (node (ref "R28") (pin "1") (pinfunction "1_1") (pintype "passive"))
      (node (ref "R29") (pin "1") (pinfunction "1_1") (pintype "passive"))
      (node (ref "R4") (pin "2") (pinfunction "2_2") (pintype "passive"))
      (node (ref "R5") (pin "2") (pinfunction "2_2") (pintype "passive"))
      (node (ref "U1") (pin "13") (pinfunction "VDD_13") (pintype "passive"))
      (node (ref "U1") (pin "8") (pinfunction "VDDIO_8") (pintype "passive"))
      (node (ref "U2") (pin "13") (pinfunction "VDDA_13") (pintype "passive"))
      (node (ref "U2") (pin "19") (pinfunction "VDD_4_19") (pintype "passive"))
      (node (ref "U2") (pin "32") (pinfunction "VDD_1_32") (pintype "passive"))
      (node (ref "U2") (pin "48") (pinfunction "VDD_2_48") (pintype "passive"))
      (node (ref "U2") (pin "64") (pinfunction "VDD_3_64") (pintype "passive"))
      (node (ref "U3") (pin "2") (pinfunction "VDD_2") (pintype "passive"))
      (node (ref "U4") (pin "2") (pinfunction "Vout_2") (pintype "passive"))
      (node (ref "U5") (pin "3") (pinfunction "WP#(IO2)_3") (pintype "passive"))
      (node (ref "U5") (pin "7") (pinfunction "HOLD#orRESET#(IO3)_7") (pintype "passive"))
      (node (ref "U5") (pin "8") (pinfunction "VCC_8") (pintype "passive"))
    )
    (net (code "66") (name "3V3_DAP") (class "Default")
      (node (ref "C22") (pin "2") (pinfunction "2_2") (pintype "passive"))
      (node (ref "C23") (pin "2") (pinfunction "2_2") (pintype "passive"))
      (node (ref "C32") (pin "2") (pinfunction "2_2") (pintype "passive"))
      (node (ref "C33") (pin "2") (pinfunction "2_2") (pintype "passive"))
      (node (ref "C34") (pin "2") (pinfunction "2_2") (pintype "passive"))
      (node (ref "C35") (pin "2") (pinfunction "2_2") (pintype "passive"))
      (node (ref "R18") (pin "2") (pinfunction "2_2") (pintype "passive"))
      (node (ref "R2") (pin "1") (pinfunction "1_1") (pintype "passive"))
      (node (ref "R24") (pin "1") (pinfunction "1_1") (pintype "passive"))
      (node (ref "U7") (pin "2") (pinfunction "Vout_2") (pintype "passive"))
      (node (ref "U8") (pin "1") (pinfunction "VBAT_1") (pintype "passive"))
      (node (ref "U8") (pin "24") (pinfunction "VDD_1_24") (pintype "passive"))
      (node (ref "U8") (pin "36") (pinfunction "VDD_2_36") (pintype "passive"))
      (node (ref "U8") (pin "48") (pinfunction "VDD_3_48") (pintype "passive"))
      (node (ref "U8") (pin "9") (pinfunction "VDDA_9") (pintype "passive"))
    )
    (net (code "67") (name "3V3_LCD") (class "Default")
      (node (ref "C14") (pin "2") (pinfunction "2_2") (pintype "passive"))
      (node (ref "C15") (pin "2") (pinfunction "2_2") (pintype "passive"))
      (node (ref "C36") (pin "2") (pinfunction "2_2") (pintype "passive"))
      (node (ref "U6") (pin "2") (pinfunction "Vout_2") (pintype "passive"))
      (node (ref "module1") (pin "1") (pinfunction "VCC_1") (pintype "passive"))
    )
    (net (code "68") (name "5V") (class "Default")
      (node (ref "C12") (pin "2") (pinfunction "2_2") (pintype "passive"))
      (node (ref "C13") (pin "2") (pinfunction "2_2") (pintype "passive"))
      (node (ref "C20") (pin "2") (pinfunction "2_2") (pintype "passive"))
      (node (ref "C21") (pin "2") (pinfunction "2_2") (pintype "passive"))
      (node (ref "C4") (pin "2") (pinfunction "2_2") (pintype "passive"))
      (node (ref "C5") (pin "2") (pinfunction "2_2") (pintype "passive"))
      (node (ref "C8") (pin "2") (pinfunction "2_2") (pintype "passive"))
      (node (ref "C9") (pin "2") (pinfunction "2_2") (pintype "passive"))
      (node (ref "F1") (pin "2") (pinfunction "2_2") (pintype "passive"))
      (node (ref "H1") (pin "1") (pinfunction "1_1") (pintype "passive"))
      (node (ref "H2") (pin "1") (pinfunction "1_1") (pintype "passive"))
      (node (ref "H3") (pin "1") (pinfunction "1_1") (pintype "passive"))
      (node (ref "H7") (pin "1") (pinfunction "1_1") (pintype "passive"))
      (node (ref "U4") (pin "3") (pinfunction "Vin_3") (pintype "passive"))
      (node (ref "U6") (pin "3") (pinfunction "Vin_3") (pintype "passive"))
      (node (ref "U7") (pin "3") (pinfunction "Vin_3") (pintype "passive"))
    )
    (net (code "69") (name "GND") (class "Default")
      (node (ref "C1") (pin "1") (pinfunction "1_1") (pintype "passive"))
      (node (ref "C10") (pin "1") (pinfunction "1_1") (pintype "passive"))
      (node (ref "C11") (pin "1") (pinfunction "1_1") (pintype "passive"))
      (node (ref "C12") (pin "1") (pinfunction "1_1") (pintype "passive"))
      (node (ref "C13") (pin "1") (pinfunction "1_1") (pintype "passive"))
      (node (ref "C14") (pin "1") (pinfunction "1_1") (pintype "passive"))
      (node (ref "C15") (pin "1") (pinfunction "1_1") (pintype "passive"))
      (node (ref "C16") (pin "1") (pinfunction "1_1") (pintype "passive"))
      (node (ref "C17") (pin "1") (pinfunction "1_1") (pintype "passive"))
      (node (ref "C18") (pin "2") (pinfunction "2_2") (pintype "passive"))
      (node (ref "C19") (pin "2") (pinfunction "2_2") (pintype "passive"))
      (node (ref "C2") (pin "2") (pinfunction "2_2") (pintype "passive"))
      (node (ref "C20") (pin "1") (pinfunction "1_1") (pintype "passive"))
      (node (ref "C21") (pin "1") (pinfunction "1_1") (pintype "passive"))
      (node (ref "C22") (pin "1") (pinfunction "1_1") (pintype "passive"))
      (node (ref "C23") (pin "1") (pinfunction "1_1") (pintype "passive"))
      (node (ref "C24") (pin "1") (pinfunction "1_1") (pintype "passive"))
      (node (ref "C25") (pin "1") (pinfunction "1_1") (pintype "passive"))
      (node (ref "C26") (pin "1") (pinfunction "1_1") (pintype "passive"))
      (node (ref "C27") (pin "1") (pinfunction "1_1") (pintype "passive"))
      (node (ref "C28") (pin "1") (pinfunction "1_1") (pintype "passive"))
      (node (ref "C29") (pin "2") (pinfunction "2_2") (pintype "passive"))
      (node (ref "C3") (pin "2") (pinfunction "2_2") (pintype "passive"))
      (node (ref "C30") (pin "1") (pinfunction "1_1") (pintype "passive"))
      (node (ref "C31") (pin "2") (pinfunction "2_2") (pintype "passive"))
      (node (ref "C32") (pin "1") (pinfunction "1_1") (pintype "passive"))
      (node (ref "C33") (pin "1") (pinfunction "1_1") (pintype "passive"))
      (node (ref "C34") (pin "1") (pinfunction "1_1") (pintype "passive"))
      (node (ref "C35") (pin "1") (pinfunction "1_1") (pintype "passive"))
      (node (ref "C36") (pin "1") (pinfunction "1_1") (pintype "passive"))
      (node (ref "C37") (pin "2") (pinfunction "2_2") (pintype "passive"))
      (node (ref "C38") (pin "1") (pinfunction "1_1") (pintype "passive"))
      (node (ref "C39") (pin "2") (pinfunction "2_2") (pintype "passive"))
      (node (ref "C4") (pin "1") (pinfunction "1_1") (pintype "passive"))
      (node (ref "C40") (pin "2") (pinfunction "2_2") (pintype "passive"))
      (node (ref "C41") (pin "2") (pinfunction "2_2") (pintype "passive"))
      (node (ref "C5") (pin "1") (pinfunction "1_1") (pintype "passive"))
      (node (ref "C6") (pin "2") (pinfunction "2_2") (pintype "passive"))
      (node (ref "C7") (pin "2") (pinfunction "2_2") (pintype "passive"))
      (node (ref "C8") (pin "1") (pinfunction "1_1") (pintype "passive"))
      (node (ref "C9") (pin "1") (pinfunction "1_1") (pintype "passive"))
      (node (ref "CARD1") (pin "10") (pinfunction "10_10") (pintype "passive"))
      (node (ref "CARD1") (pin "11") (pinfunction "11_11") (pintype "passive"))
      (node (ref "CARD1") (pin "12") (pinfunction "12_12") (pintype "passive"))
      (node (ref "CARD1") (pin "13") (pinfunction "13_13") (pintype "passive"))
      (node (ref "CARD1") (pin "6") (pinfunction "VSS_6") (pintype "passive"))
      (node (ref "CN1") (pin "1") (pinfunction "GND_1") (pintype "passive"))
      (node (ref "CN1") (pin "12") (pinfunction "GND_12") (pintype "passive"))
      (node (ref "H1") (pin "4") (pinfunction "4_4") (pintype "passive"))
      (node (ref "H2") (pin "4") (pinfunction "4_4") (pintype "passive"))
      (node (ref "H3") (pin "4") (pinfunction "4_4") (pintype "passive"))
      (node (ref "H4") (pin "3") (pinfunction "3_3") (pintype "passive"))
      (node (ref "H5") (pin "3") (pinfunction "3_3") (pintype "passive"))
      (node (ref "H6") (pin "3") (pinfunction "3_3") (pintype "passive"))
      (node (ref "H7") (pin "4") (pinfunction "4_4") (pintype "passive"))
      (node (ref "K1") (pin "1") (pinfunction "1_1") (pintype "passive"))
      (node (ref "K2") (pin "1") (pinfunction "1_1") (pintype "passive"))
      (node (ref "K4") (pin "2") (pinfunction "2_2") (pintype "passive"))
      (node (ref "LED4") (pin "1") (pinfunction "1_1") (pintype "passive"))
      (node (ref "LED5") (pin "1") (pinfunction "1_1") (pintype "passive"))
      (node (ref "Q1") (pin "2") (pinfunction "2_2") (pintype "passive"))
      (node (ref "R1") (pin "2") (pinfunction "2_2") (pintype "passive"))
      (node (ref "R10") (pin "2") (pinfunction "2_2") (pintype "passive"))
      (node (ref "R17") (pin "1") (pinfunction "1_1") (pintype "passive"))
      (node (ref "R21") (pin "3") (pinfunction "3_3") (pintype "passive"))
      (node (ref "R22") (pin "1") (pinfunction "1_1") (pintype "passive"))
      (node (ref "R23") (pin "1") (pinfunction "1_1") (pintype "passive"))
      (node (ref "R3") (pin "2") (pinfunction "2_2") (pintype "passive"))
      (node (ref "R9") (pin "2") (pinfunction "2_2") (pintype "passive"))
      (node (ref "U1") (pin "11") (pinfunction "FSYNC_11") (pintype "passive"))
      (node (ref "U1") (pin "18") (pinfunction "GND_18") (pintype "passive"))
      (node (ref "U1") (pin "20") (pinfunction "RESV_20") (pintype "passive"))
      (node (ref "U10") (pin "2") (pinfunction "2_2") (pintype "passive"))
      (node (ref "U2") (pin "12") (pinfunction "VSSA_12") (pintype "passive"))
      (node (ref "U2") (pin "18") (pinfunction "VSS_4_18") (pintype "passive"))
      (node (ref "U2") (pin "31") (pinfunction "VSS_1_31") (pintype "passive"))
      (node (ref "U2") (pin "47") (pinfunction "VSS_2_47") (pintype "passive"))
      (node (ref "U2") (pin "63") (pinfunction "VSS_3_63") (pintype "passive"))
      (node (ref "U3") (pin "5") (pinfunction "GND_5") (pintype "passive"))
      (node (ref "U4") (pin "1") (pinfunction "GND_1") (pintype "passive"))
      (node (ref "U5") (pin "4") (pinfunction "GND_4") (pintype "passive"))
      (node (ref "U6") (pin "1") (pinfunction "GND_1") (pintype "passive"))
      (node (ref "U7") (pin "1") (pinfunction "GND_1") (pintype "passive"))
      (node (ref "U8") (pin "23") (pinfunction "VSS_1_23") (pintype "passive"))
      (node (ref "U8") (pin "35") (pinfunction "VSS_2_35") (pintype "passive"))
      (node (ref "U8") (pin "47") (pinfunction "VSS_3_47") (pintype "passive"))
      (node (ref "U8") (pin "8") (pinfunction "VSSA_8") (pintype "passive"))
      (node (ref "U9") (pin "1") (pinfunction "E_1") (pintype "passive"))
      (node (ref "X2") (pin "2") (pinfunction "2_2") (pintype "passive"))
      (node (ref "X2") (pin "4") (pinfunction "4_4") (pintype "passive"))
      (node (ref "X3") (pin "2") (pinfunction "2_2") (pintype "passive"))
      (node (ref "X3") (pin "4") (pinfunction "4_4") (pintype "passive"))
      (node (ref "module1") (pin "2") (pinfunction "GND_2") (pintype "passive"))
    )
    (net (code "70") (name "Net-(BUZZER1-Pad2)") (class "Default")
      (node (ref "BUZZER1") (pin "2") (pinfunction "2_2") (pintype "passive"))
      (node (ref "D1") (pin "1") (pinfunction "1_1") (pintype "passive"))
      (node (ref "Q1") (pin "3") (pinfunction "3_3") (pintype "passive"))
    )
    (net (code "71") (name "Net-(CN1-CC1)") (class "Default")
      (node (ref "CN1") (pin "4") (pinfunction "CC1_4") (pintype "passive"))
      (node (ref "R3") (pin "1") (pinfunction "1_1") (pintype "passive"))
    )
    (net (code "72") (name "Net-(CN1-CC2)") (class "Default")
      (node (ref "CN1") (pin "10") (pinfunction "CC2_10") (pintype "passive"))
      (node (ref "R1") (pin "1") (pinfunction "1_1") (pintype "passive"))
    )
    (net (code "73") (name "Net-(CN1-VBUS-Pad11)") (class "Default")
      (node (ref "CN1") (pin "11") (pinfunction "VBUS_11") (pintype "passive"))
      (node (ref "CN1") (pin "2") (pinfunction "VBUS_2") (pintype "passive"))
      (node (ref "F1") (pin "1") (pinfunction "1_1") (pintype "passive"))
    )
    (net (code "74") (name "Net-(D2-Pad1)") (class "Default")
      (node (ref "D2") (pin "1") (pinfunction "1_1") (pintype "passive"))
      (node (ref "U10") (pin "1") (pinfunction "1_1") (pintype "passive"))
    )
    (net (code "75") (name "Net-(LED1-Pad1)") (class "Default")
      (node (ref "LED1") (pin "1") (pinfunction "1_1") (pintype "passive"))
      (node (ref "R6") (pin "2") (pinfunction "2_2") (pintype "passive"))
    )
    (net (code "76") (name "Net-(LED2-Pad1)") (class "Default")
      (node (ref "LED2") (pin "1") (pinfunction "1_1") (pintype "passive"))
      (node (ref "R7") (pin "1") (pinfunction "1_1") (pintype "passive"))
    )
    (net (code "77") (name "Net-(LED3-Pad1)") (class "Default")
      (node (ref "LED3") (pin "1") (pinfunction "1_1") (pintype "passive"))
      (node (ref "R8") (pin "1") (pinfunction "1_1") (pintype "passive"))
    )
    (net (code "78") (name "Net-(LED4-Pad2)") (class "Default")
      (node (ref "LED4") (pin "2") (pinfunction "2_2") (pintype "passive"))
      (node (ref "R12") (pin "1") (pinfunction "1_1") (pintype "passive"))
    )
    (net (code "79") (name "Net-(LED5-Pad2)") (class "Default")
      (node (ref "LED5") (pin "2") (pinfunction "2_2") (pintype "passive"))
      (node (ref "R13") (pin "1") (pinfunction "1_1") (pintype "passive"))
    )
    (net (code "80") (name "Net-(Q1-Pad1)") (class "Default")
      (node (ref "Q1") (pin "1") (pinfunction "1_1") (pintype "passive"))
      (node (ref "R14") (pin "2") (pinfunction "2_2") (pintype "passive"))
    )
    (net (code "81") (name "Net-(U1-REGOUT)") (class "Default")
      (node (ref "C41") (pin "1") (pinfunction "1_1") (pintype "passive"))
      (node (ref "U1") (pin "10") (pinfunction "REGOUT_10") (pintype "passive"))
    )
    (net (code "82") (name "unconnected-(BUZZER1-Pad3)") (class "Default")
      (node (ref "BUZZER1") (pin "3") (pinfunction "3_3") (pintype "passive+no_connect"))
    )
    (net (code "83") (name "unconnected-(BUZZER1-Pad4)") (class "Default")
      (node (ref "BUZZER1") (pin "4") (pinfunction "4_4") (pintype "passive+no_connect"))
    )
    (net (code "84") (name "unconnected-(CN1-SBU1-Pad9)") (class "Default")
      (node (ref "CN1") (pin "9") (pinfunction "SBU1_9") (pintype "passive+no_connect"))
    )
    (net (code "85") (name "unconnected-(CN1-SBU2-Pad3)") (class "Default")
      (node (ref "CN1") (pin "3") (pinfunction "SBU2_3") (pintype "passive+no_connect"))
    )
    (net (code "86") (name "unconnected-(CN1-SHELL-Pad13)") (class "Default")
      (node (ref "CN1") (pin "13") (pinfunction "SHELL_13") (pintype "passive+no_connect"))
    )
    (net (code "87") (name "unconnected-(CN1-SHELL-Pad14)") (class "Default")
      (node (ref "CN1") (pin "14") (pinfunction "SHELL_14") (pintype "passive+no_connect"))
    )
    (net (code "88") (name "unconnected-(U1-AUX_CL-Pad7)") (class "Default")
      (node (ref "U1") (pin "7") (pinfunction "AUX_CL_7") (pintype "passive+no_connect"))
    )
    (net (code "89") (name "unconnected-(U1-AUX_DA-Pad21)") (class "Default")
      (node (ref "U1") (pin "21") (pinfunction "AUX_DA_21") (pintype "passive+no_connect"))
    )
    (net (code "90") (name "unconnected-(U1-EP-Pad25)") (class "Default")
      (node (ref "U1") (pin "25") (pinfunction "EP_25") (pintype "passive+no_connect"))
    )
    (net (code "91") (name "unconnected-(U1-NC-Pad1)") (class "Default")
      (node (ref "U1") (pin "1") (pinfunction "NC_1") (pintype "passive+no_connect"))
    )
    (net (code "92") (name "unconnected-(U1-NC-Pad2)") (class "Default")
      (node (ref "U1") (pin "2") (pinfunction "NC_2") (pintype "passive+no_connect"))
    )
    (net (code "93") (name "unconnected-(U1-NC-Pad3)") (class "Default")
      (node (ref "U1") (pin "3") (pinfunction "NC_3") (pintype "passive+no_connect"))
    )
    (net (code "94") (name "unconnected-(U1-NC-Pad4)") (class "Default")
      (node (ref "U1") (pin "4") (pinfunction "NC_4") (pintype "passive+no_connect"))
    )
    (net (code "95") (name "unconnected-(U1-NC-Pad5)") (class "Default")
      (node (ref "U1") (pin "5") (pinfunction "NC_5") (pintype "passive+no_connect"))
    )
    (net (code "96") (name "unconnected-(U1-NC-Pad6)") (class "Default")
      (node (ref "U1") (pin "6") (pinfunction "NC_6") (pintype "passive+no_connect"))
    )
    (net (code "97") (name "unconnected-(U1-NC-Pad14)") (class "Default")
      (node (ref "U1") (pin "14") (pinfunction "NC_14") (pintype "passive+no_connect"))
    )
    (net (code "98") (name "unconnected-(U1-NC-Pad15)") (class "Default")
      (node (ref "U1") (pin "15") (pinfunction "NC_15") (pintype "passive+no_connect"))
    )
    (net (code "99") (name "unconnected-(U1-NC-Pad16)") (class "Default")
      (node (ref "U1") (pin "16") (pinfunction "NC_16") (pintype "passive+no_connect"))
    )
    (net (code "100") (name "unconnected-(U1-NC-Pad17)") (class "Default")
      (node (ref "U1") (pin "17") (pinfunction "NC_17") (pintype "passive+no_connect"))
    )
    (net (code "101") (name "unconnected-(U1-RESV-Pad19)") (class "Default")
      (node (ref "U1") (pin "19") (pinfunction "RESV_19") (pintype "passive+no_connect"))
    )
    (net (code "102") (name "unconnected-(U2-PA8-Pad41)") (class "Default")
      (node (ref "U2") (pin "41") (pinfunction "PA8_41") (pintype "passive"))
    )
    (net (code "103") (name "unconnected-(U2-PB5-Pad57)") (class "Default")
      (node (ref "U2") (pin "57") (pinfunction "PB5_57") (pintype "passive"))
    )
    (net (code "104") (name "unconnected-(U2-PC13-TAMPER-RTC-Pad2)") (class "Default")
      (node (ref "U2") (pin "2") (pinfunction "PC13-TAMPER-RTC_2") (pintype "passive"))
    )
    (net (code "105") (name "unconnected-(U3-NC-Pad1)") (class "Default")
      (node (ref "U3") (pin "1") (pinfunction "NC_1") (pintype "passive+no_connect"))
    )
    (net (code "106") (name "unconnected-(U3-NC-Pad6)") (class "Default")
      (node (ref "U3") (pin "6") (pinfunction "NC_6") (pintype "passive+no_connect"))
    )
    (net (code "107") (name "unconnected-(U8-PA0-WKUP-Pad10)") (class "Default")
      (node (ref "U8") (pin "10") (pinfunction "PA0-WKUP_10") (pintype "passive"))
    )
    (net (code "108") (name "unconnected-(U8-PA1-Pad11)") (class "Default")
      (node (ref "U8") (pin "11") (pinfunction "PA1_11") (pintype "passive"))
    )
    (net (code "109") (name "unconnected-(U8-PA3-Pad13)") (class "Default")
      (node (ref "U8") (pin "13") (pinfunction "PA3_13") (pintype "passive"))
    )
    (net (code "110") (name "unconnected-(U8-PA5-Pad15)") (class "Default")
      (node (ref "U8") (pin "15") (pinfunction "PA5_15") (pintype "passive"))
    )
    (net (code "111") (name "unconnected-(U8-PA7-Pad17)") (class "Default")
      (node (ref "U8") (pin "17") (pinfunction "PA7_17") (pintype "passive"))
    )
    (net (code "112") (name "unconnected-(U8-PA8-Pad29)") (class "Default")
      (node (ref "U8") (pin "29") (pinfunction "PA8_29") (pintype "passive"))
    )
    (net (code "113") (name "unconnected-(U8-PA15-Pad38)") (class "Default")
      (node (ref "U8") (pin "38") (pinfunction "PA15_38") (pintype "passive"))
    )
    (net (code "114") (name "unconnected-(U8-PB0-Pad18)") (class "Default")
      (node (ref "U8") (pin "18") (pinfunction "PB0_18") (pintype "passive"))
    )
    (net (code "115") (name "unconnected-(U8-PB1-Pad19)") (class "Default")
      (node (ref "U8") (pin "19") (pinfunction "PB1_19") (pintype "passive"))
    )
    (net (code "116") (name "unconnected-(U8-PB3-Pad39)") (class "Default")
      (node (ref "U8") (pin "39") (pinfunction "PB3_39") (pintype "passive"))
    )
    (net (code "117") (name "unconnected-(U8-PB4-Pad40)") (class "Default")
      (node (ref "U8") (pin "40") (pinfunction "PB4_40") (pintype "passive"))
    )
    (net (code "118") (name "unconnected-(U8-PB5-Pad41)") (class "Default")
      (node (ref "U8") (pin "41") (pinfunction "PB5_41") (pintype "passive"))
    )
    (net (code "119") (name "unconnected-(U8-PB6-Pad42)") (class "Default")
      (node (ref "U8") (pin "42") (pinfunction "PB6_42") (pintype "passive"))
    )
    (net (code "120") (name "unconnected-(U8-PB7-Pad43)") (class "Default")
      (node (ref "U8") (pin "43") (pinfunction "PB7_43") (pintype "passive"))
    )
    (net (code "121") (name "unconnected-(U8-PB9-Pad46)") (class "Default")
      (node (ref "U8") (pin "46") (pinfunction "PB9_46") (pintype "passive"))
    )
    (net (code "122") (name "unconnected-(U8-PB10-Pad21)") (class "Default")
      (node (ref "U8") (pin "21") (pinfunction "PB10_21") (pintype "passive"))
    )
    (net (code "123") (name "unconnected-(U8-PB11-Pad22)") (class "Default")
      (node (ref "U8") (pin "22") (pinfunction "PB11_22") (pintype "passive"))
    )
    (net (code "124") (name "unconnected-(U8-PB13-Pad26)") (class "Default")
      (node (ref "U8") (pin "26") (pinfunction "PB13_26") (pintype "passive"))
    )
    (net (code "125") (name "unconnected-(U8-PB14-Pad27)") (class "Default")
      (node (ref "U8") (pin "27") (pinfunction "PB14_27") (pintype "passive"))
    )
    (net (code "126") (name "unconnected-(U8-PB15-Pad28)") (class "Default")
      (node (ref "U8") (pin "28") (pinfunction "PB15_28") (pintype "passive"))
    )
    (net (code "127") (name "unconnected-(U8-PC13-TAMPER-RTC-Pad2)") (class "Default")
      (node (ref "U8") (pin "2") (pinfunction "PC13-TAMPER-RTC_2") (pintype "passive"))
    )
    (net (code "128") (name "unconnected-(U8-PC14-OSC32_IN-Pad3)") (class "Default")
      (node (ref "U8") (pin "3") (pinfunction "PC14-OSC32_IN_3") (pintype "passive"))
    )
    (net (code "129") (name "unconnected-(U8-PC15-OSC32_OUT-Pad4)") (class "Default")
      (node (ref "U8") (pin "4") (pinfunction "PC15-OSC32_OUT_4") (pintype "passive"))
    )
    (net (code "130") (name "unconnected-(module1-NC-Pad13)") (class "Default")
      (node (ref "module1") (pin "13") (pinfunction "NC_13") (pintype "passive+no_connect"))
    )
  )
)
